# x-OSC_Programmer.net
KiCad netlist of a schematic drawn in EAGLE
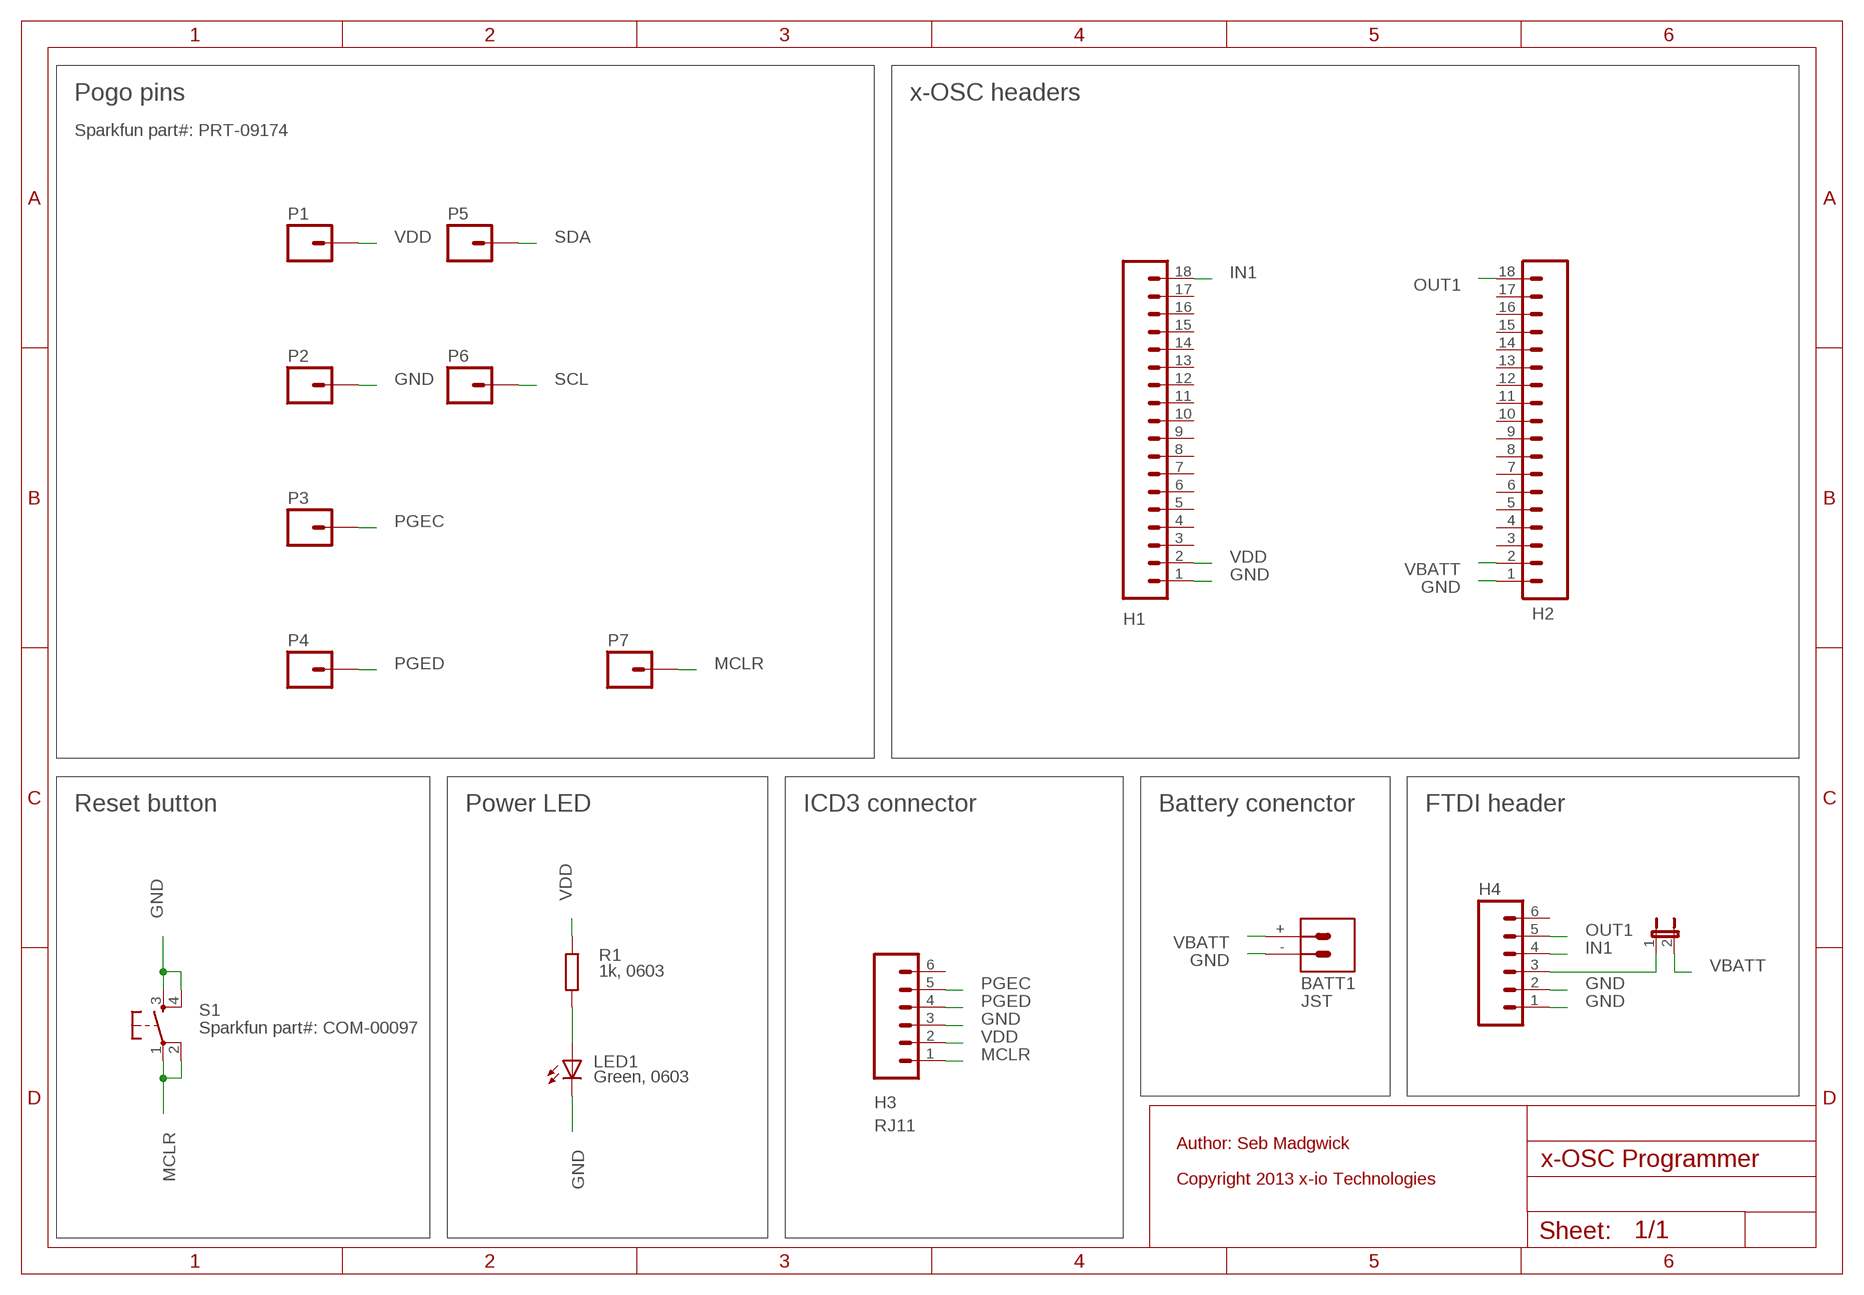
[diagram p0: schematic, sheet 1]

(export (version "E")
  (design (tool "Eeschema 10.0.6"))
  (components
    (comp (ref "BATT1")
      (value "JST")
      (footprint "eagle-import:JST-R_A")
      (libsource (lib "eagle-import") (part "JST"))
    )
    (comp (ref "H1")
      (value "M18_")
      (footprint "eagle-import:1X18")
      (libsource (lib "eagle-import") (part "M18_"))
    )
    (comp (ref "H2")
      (value "M18_")
      (footprint "eagle-import:1X18")
      (libsource (lib "eagle-import") (part "M18_"))
    )
    (comp (ref "H3")
      (value "RJ11")
      (footprint "eagle-import:RJ11-6")
      (libsource (lib "eagle-import") (part "RJ11-6PTH"))
    )
    (comp (ref "H4")
      (value "M06SIP")
      (footprint "eagle-import:1X06")
      (libsource (lib "eagle-import") (part "M06SIP"))
    )
    (comp (ref "JP1")
      (value "JUMPER-2SMD-NO")
      (footprint "eagle-import:SJ_2S-NO")
      (libsource (lib "eagle-import") (part "JUMPER-2SMD-NO"))
    )
    (comp (ref "LED1")
      (value "Green, 0603")
      (footprint "eagle-import:LED-0603")
      (libsource (lib "eagle-import") (part "LED0603"))
    )
    (comp (ref "P1")
      (value "M01PTH")
      (footprint "eagle-import:1X01")
      (libsource (lib "eagle-import") (part "M01PTH"))
    )
    (comp (ref "P2")
      (value "M01PTH")
      (footprint "eagle-import:1X01")
      (libsource (lib "eagle-import") (part "M01PTH"))
    )
    (comp (ref "P3")
      (value "M01PTH")
      (footprint "eagle-import:1X01")
      (libsource (lib "eagle-import") (part "M01PTH"))
    )
    (comp (ref "P4")
      (value "M01PTH")
      (footprint "eagle-import:1X01")
      (libsource (lib "eagle-import") (part "M01PTH"))
    )
    (comp (ref "P5")
      (value "M01PTH")
      (footprint "eagle-import:1X01")
      (libsource (lib "eagle-import") (part "M01PTH"))
    )
    (comp (ref "P6")
      (value "M01PTH")
      (footprint "eagle-import:1X01")
      (libsource (lib "eagle-import") (part "M01PTH"))
    )
    (comp (ref "P7")
      (value "M01PTH")
      (footprint "eagle-import:1X01")
      (libsource (lib "eagle-import") (part "M01PTH"))
    )
    (comp (ref "R1")
      (value "1k, 0603")
      (footprint "eagle-import:R0402")
      (libsource (lib "eagle-import") (part "R-EU_R0402"))
    )
    (comp (ref "S1")
      (value "Sparkfun part#: COM-00097")
      (footprint "eagle-import:TACTILE-PTH")
      (libsource (lib "eagle-import") (part "TAC_SWITCHPTH"))
    )
  )
  (nets
    (net (code "1") (name "/GND") (class "Default")
      (node (ref "BATT1") (pin "-") (pintype "bidirectional"))
      (node (ref "H1") (pin "1") (pinfunction "1_1") (pintype "passive"))
      (node (ref "H2") (pin "1") (pinfunction "1_1") (pintype "passive"))
      (node (ref "H3") (pin "3") (pinfunction "3_3") (pintype "passive"))
      (node (ref "H4") (pin "1") (pinfunction "1_1") (pintype "passive"))
      (node (ref "H4") (pin "2") (pinfunction "2_2") (pintype "passive"))
      (node (ref "LED1") (pin "C") (pinfunction "C_C") (pintype "passive"))
      (node (ref "P2") (pin "1") (pinfunction "1_1") (pintype "passive"))
      (node (ref "S1") (pin "3") (pinfunction "3_3") (pintype "passive"))
      (node (ref "S1") (pin "4") (pinfunction "4_4") (pintype "passive"))
    )
    (net (code "2") (name "/IN1") (class "Default")
      (node (ref "H1") (pin "18") (pinfunction "18_18") (pintype "passive"))
      (node (ref "H4") (pin "4") (pinfunction "4_4") (pintype "passive"))
    )
    (net (code "3") (name "/MCLR") (class "Default")
      (node (ref "H3") (pin "1") (pinfunction "1_1") (pintype "passive"))
      (node (ref "P7") (pin "1") (pinfunction "1_1") (pintype "passive"))
      (node (ref "S1") (pin "1") (pinfunction "1_1") (pintype "passive"))
      (node (ref "S1") (pin "2") (pinfunction "2_2") (pintype "passive"))
    )
    (net (code "4") (name "/OUT1") (class "Default")
      (node (ref "H2") (pin "18") (pinfunction "18_18") (pintype "passive"))
      (node (ref "H4") (pin "5") (pinfunction "5_5") (pintype "passive"))
    )
    (net (code "5") (name "/PGEC") (class "Default")
      (node (ref "H3") (pin "5") (pinfunction "5_5") (pintype "passive"))
      (node (ref "P3") (pin "1") (pinfunction "1_1") (pintype "passive"))
    )
    (net (code "6") (name "/PGED") (class "Default")
      (node (ref "H3") (pin "4") (pinfunction "4_4") (pintype "passive"))
      (node (ref "P4") (pin "1") (pinfunction "1_1") (pintype "passive"))
    )
    (net (code "7") (name "/SCL") (class "Default")
      (node (ref "P6") (pin "1") (pinfunction "1_1") (pintype "passive"))
    )
    (net (code "8") (name "/SDA") (class "Default")
      (node (ref "P5") (pin "1") (pinfunction "1_1") (pintype "passive"))
    )
    (net (code "9") (name "/VBATT") (class "Default")
      (node (ref "BATT1") (pin "+") (pintype "bidirectional"))
      (node (ref "H2") (pin "2") (pinfunction "2_2") (pintype "passive"))
      (node (ref "JP1") (pin "2") (pinfunction "2_2") (pintype "passive"))
    )
    (net (code "10") (name "/VDD") (class "Default")
      (node (ref "H1") (pin "2") (pinfunction "2_2") (pintype "passive"))
      (node (ref "H3") (pin "2") (pinfunction "2_2") (pintype "passive"))
      (node (ref "P1") (pin "1") (pinfunction "1_1") (pintype "passive"))
      (node (ref "R1") (pin "1") (pinfunction "1_1") (pintype "passive"))
    )
    (net (code "11") (name "Net-(H4-Pad3)") (class "Default")
      (node (ref "H4") (pin "3") (pinfunction "3_3") (pintype "passive"))
      (node (ref "JP1") (pin "1") (pinfunction "1_1") (pintype "passive"))
    )
    (net (code "12") (name "Net-(LED1-PadA)") (class "Default")
      (node (ref "LED1") (pin "A") (pinfunction "A_A") (pintype "passive"))
      (node (ref "R1") (pin "2") (pinfunction "2_2") (pintype "passive"))
    )
    (net (code "13") (name "unconnected-(H1-Pad3)") (class "Default")
      (node (ref "H1") (pin "3") (pinfunction "3_3") (pintype "passive"))
    )
    (net (code "14") (name "unconnected-(H1-Pad4)") (class "Default")
      (node (ref "H1") (pin "4") (pinfunction "4_4") (pintype "passive"))
    )
    (net (code "15") (name "unconnected-(H1-Pad5)") (class "Default")
      (node (ref "H1") (pin "5") (pinfunction "5_5") (pintype "passive"))
    )
    (net (code "16") (name "unconnected-(H1-Pad6)") (class "Default")
      (node (ref "H1") (pin "6") (pinfunction "6_6") (pintype "passive"))
    )
    (net (code "17") (name "unconnected-(H1-Pad7)") (class "Default")
      (node (ref "H1") (pin "7") (pinfunction "7_7") (pintype "passive"))
    )
    (net (code "18") (name "unconnected-(H1-Pad8)") (class "Default")
      (node (ref "H1") (pin "8") (pinfunction "8_8") (pintype "passive"))
    )
    (net (code "19") (name "unconnected-(H1-Pad9)") (class "Default")
      (node (ref "H1") (pin "9") (pinfunction "9_9") (pintype "passive"))
    )
    (net (code "20") (name "unconnected-(H1-Pad10)") (class "Default")
      (node (ref "H1") (pin "10") (pinfunction "10_10") (pintype "passive"))
    )
    (net (code "21") (name "unconnected-(H1-Pad11)") (class "Default")
      (node (ref "H1") (pin "11") (pinfunction "11_11") (pintype "passive"))
    )
    (net (code "22") (name "unconnected-(H1-Pad12)") (class "Default")
      (node (ref "H1") (pin "12") (pinfunction "12_12") (pintype "passive"))
    )
    (net (code "23") (name "unconnected-(H1-Pad13)") (class "Default")
      (node (ref "H1") (pin "13") (pinfunction "13_13") (pintype "passive"))
    )
    (net (code "24") (name "unconnected-(H1-Pad14)") (class "Default")
      (node (ref "H1") (pin "14") (pinfunction "14_14") (pintype "passive"))
    )
    (net (code "25") (name "unconnected-(H1-Pad15)") (class "Default")
      (node (ref "H1") (pin "15") (pinfunction "15_15") (pintype "passive"))
    )
    (net (code "26") (name "unconnected-(H1-Pad16)") (class "Default")
      (node (ref "H1") (pin "16") (pinfunction "16_16") (pintype "passive"))
    )
    (net (code "27") (name "unconnected-(H1-Pad17)") (class "Default")
      (node (ref "H1") (pin "17") (pinfunction "17_17") (pintype "passive"))
    )
    (net (code "28") (name "unconnected-(H2-Pad3)") (class "Default")
      (node (ref "H2") (pin "3") (pinfunction "3_3") (pintype "passive"))
    )
    (net (code "29") (name "unconnected-(H2-Pad4)") (class "Default")
      (node (ref "H2") (pin "4") (pinfunction "4_4") (pintype "passive"))
    )
    (net (code "30") (name "unconnected-(H2-Pad5)") (class "Default")
      (node (ref "H2") (pin "5") (pinfunction "5_5") (pintype "passive"))
    )
    (net (code "31") (name "unconnected-(H2-Pad6)") (class "Default")
      (node (ref "H2") (pin "6") (pinfunction "6_6") (pintype "passive"))
    )
    (net (code "32") (name "unconnected-(H2-Pad7)") (class "Default")
      (node (ref "H2") (pin "7") (pinfunction "7_7") (pintype "passive"))
    )
    (net (code "33") (name "unconnected-(H2-Pad8)") (class "Default")
      (node (ref "H2") (pin "8") (pinfunction "8_8") (pintype "passive"))
    )
    (net (code "34") (name "unconnected-(H2-Pad9)") (class "Default")
      (node (ref "H2") (pin "9") (pinfunction "9_9") (pintype "passive"))
    )
    (net (code "35") (name "unconnected-(H2-Pad10)") (class "Default")
      (node (ref "H2") (pin "10") (pinfunction "10_10") (pintype "passive"))
    )
    (net (code "36") (name "unconnected-(H2-Pad11)") (class "Default")
      (node (ref "H2") (pin "11") (pinfunction "11_11") (pintype "passive"))
    )
    (net (code "37") (name "unconnected-(H2-Pad12)") (class "Default")
      (node (ref "H2") (pin "12") (pinfunction "12_12") (pintype "passive"))
    )
    (net (code "38") (name "unconnected-(H2-Pad13)") (class "Default")
      (node (ref "H2") (pin "13") (pinfunction "13_13") (pintype "passive"))
    )
    (net (code "39") (name "unconnected-(H2-Pad14)") (class "Default")
      (node (ref "H2") (pin "14") (pinfunction "14_14") (pintype "passive"))
    )
    (net (code "40") (name "unconnected-(H2-Pad15)") (class "Default")
      (node (ref "H2") (pin "15") (pinfunction "15_15") (pintype "passive"))
    )
    (net (code "41") (name "unconnected-(H2-Pad16)") (class "Default")
      (node (ref "H2") (pin "16") (pinfunction "16_16") (pintype "passive"))
    )
    (net (code "42") (name "unconnected-(H2-Pad17)") (class "Default")
      (node (ref "H2") (pin "17") (pinfunction "17_17") (pintype "passive"))
    )
    (net (code "43") (name "unconnected-(H3-Pad6)") (class "Default")
      (node (ref "H3") (pin "6") (pinfunction "6_6") (pintype "passive"))
    )
    (net (code "44") (name "unconnected-(H4-Pad6)") (class "Default")
      (node (ref "H4") (pin "6") (pinfunction "6_6") (pintype "passive"))
    )
  )
)
